# Power4.net
KiCad netlist of a schematic drawn in Altium Designer
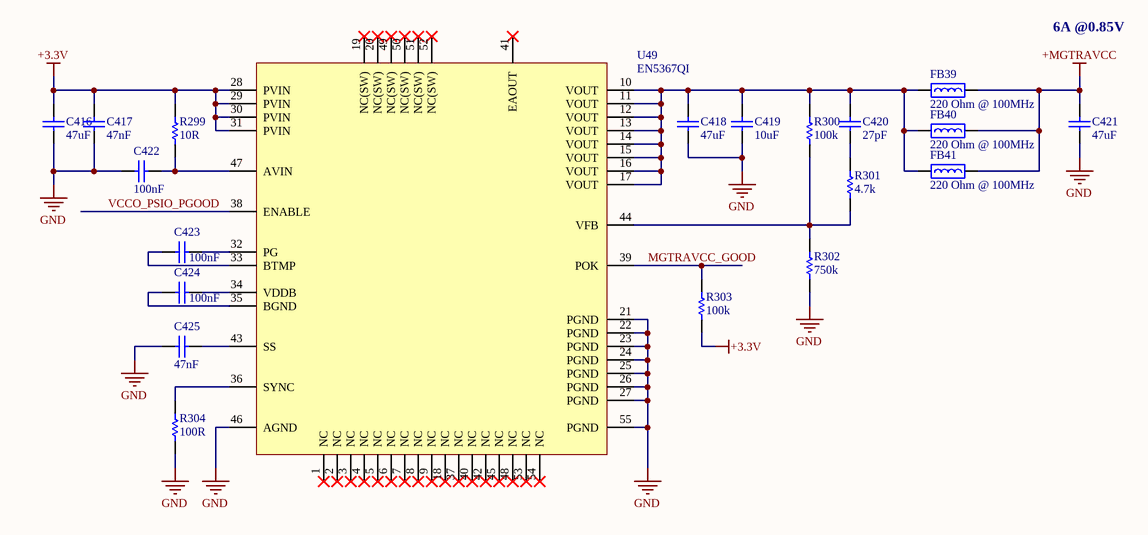
[diagram p0: Power4.SchDoc]

(export (version "E")
  (design (tool "Eeschema 10.0.6"))
  (components
    (comp (ref "C416")
      (value "47uF")
      (footprint "CAPC3216L_1206")
      (description "CAP CER 47UF 25V X5R 1206")
      (fields (field (name "VOLTAGE") "25V") (field (name "TOLERANCE") "20%"))
      (libsource (lib "Ultrascale_SchLib") (part "CAPCER1206X5R47U25V_20T"))
    )
    (comp (ref "C417")
      (value "47nF")
      (footprint "CAPC2012L_0805")
      (description "CAP CER 0.047UF 50V X7R 0805")
      (fields (field (name "VOLTAGE") "50V") (field (name "TOLERANCE") "10%"))
      (libsource (lib "Ultrascale_SchLib") (part "CAPCER0805X5R47N50V_10T"))
    )
    (comp (ref "C418")
      (value "47uF")
      (footprint "CAPC3216L_1206")
      (description "CAP CER 47UF 25V X5R 1206")
      (fields (field (name "VOLTAGE") "25V") (field (name "TOLERANCE") "20%"))
      (libsource (lib "Ultrascale_SchLib") (part "CAPCER1206X5R47U25V_20T"))
    )
    (comp (ref "C419")
      (value "10uF")
      (footprint "CAPC1005L_0402")
      (description "CAP CER 10UF 10V X5R 0402")
      (fields (field (name "VOLTAGE") "10V") (field (name "TOLERANCE") "20%"))
      (libsource (lib "Ultrascale_SchLib") (part "CAPCER0402X5R10U10V_20T"))
    )
    (comp (ref "C420")
      (value "27pF")
      (footprint "CAPC1005L_0402")
      (description "CAP CER 27PF 50V C0G/NP0 0402")
      (fields (field (name "VOLTAGE") "50V") (field (name "TOLERANCE") "5%"))
      (libsource (lib "Ultrascale_SchLib") (part "CAPCER0402C0G27P50V_5T"))
    )
    (comp (ref "C421")
      (value "47uF")
      (footprint "CAPC3216L_1206")
      (description "CAP CER 47UF 25V X5R 1206")
      (fields (field (name "VOLTAGE") "25V") (field (name "TOLERANCE") "20%"))
      (libsource (lib "Ultrascale_SchLib") (part "CAPCER1206X5R47U25V_20T"))
    )
    (comp (ref "C422")
      (value "100nF")
      (footprint "CAPC1005L_0402")
      (description "CAP CER 0.1UF 25V X7R 0402")
      (fields (field (name "VOLTAGE") "25V") (field (name "TOLERANCE") "10%"))
      (libsource (lib "Ultrascale_SchLib") (part "CAPCER0402X7R100N25V_10T"))
    )
    (comp (ref "C423")
      (value "100nF")
      (footprint "CAPC1005L_0402")
      (description "CAP CER 0.1UF 25V X7R 0402")
      (fields (field (name "VOLTAGE") "25V") (field (name "TOLERANCE") "10%"))
      (libsource (lib "Ultrascale_SchLib") (part "CAPCER0402X7R100N25V_10T"))
    )
    (comp (ref "C424")
      (value "100nF")
      (footprint "CAPC1005L_0402")
      (description "CAP CER 0.1UF 25V X7R 0402")
      (fields (field (name "VOLTAGE") "25V") (field (name "TOLERANCE") "10%"))
      (libsource (lib "Ultrascale_SchLib") (part "CAPCER0402X7R100N25V_10T"))
    )
    (comp (ref "C425")
      (value "47nF")
      (footprint "CAPC2012L_0805")
      (description "CAP CER 0.047UF 50V X7R 0805")
      (fields (field (name "VOLTAGE") "50V") (field (name "TOLERANCE") "10%"))
      (libsource (lib "Ultrascale_SchLib") (part "CAPCER0805X5R47N50V_10T"))
    )
    (comp (ref "FB39")
      (value "BEAD0603_220_2A5_40M")
      (footprint "INDC1608N_0603")
      (description "FERRITE BEAD 220 OHM 0603 1LN")
      (fields (field (name "IMPEDANCE @ FREQUENCY") "220 Ohm @ 100MHz"))
      (libsource (lib "Ultrascale_SchLib") (part "BEAD0603_220_2A5_40M"))
    )
    (comp (ref "FB40")
      (value "BEAD0603_220_2A5_40M")
      (footprint "INDC1608N_0603")
      (description "FERRITE BEAD 220 OHM 0603 1LN")
      (fields (field (name "IMPEDANCE @ FREQUENCY") "220 Ohm @ 100MHz"))
      (libsource (lib "Ultrascale_SchLib") (part "BEAD0603_220_2A5_40M"))
    )
    (comp (ref "FB41")
      (value "BEAD0603_220_2A5_40M")
      (footprint "INDC1608N_0603")
      (description "FERRITE BEAD 220 OHM 0603 1LN")
      (fields (field (name "IMPEDANCE @ FREQUENCY") "220 Ohm @ 100MHz"))
      (libsource (lib "Ultrascale_SchLib") (part "BEAD0603_220_2A5_40M"))
    )
    (comp (ref "R299")
      (value "10R")
      (footprint "RESC1005L_0402")
      (description "RES SMD 10 OHM 1% 1/10W 0402")
      (fields (field (name "POWER") "1/10W") (field (name "TOLERANCE") "1%"))
      (libsource (lib "Ultrascale_SchLib") (part "RES0402_10R_0W1_1T"))
    )
    (comp (ref "R300")
      (value "100k")
      (footprint "RESC1005L_0402")
      (description "RES SMD 100K OHM 1% 1/5W 0402")
      (fields (field (name "POWER") "1/5W") (field (name "TOLERANCE") "1%"))
      (libsource (lib "Ultrascale_SchLib") (part "RES0402_100K_0W2_1T"))
    )
    (comp (ref "R301")
      (value "4.7k")
      (footprint "RESC1005L_0402")
      (description "RES SMD 4.7K OHM 1% 1/10W 0402")
      (fields (field (name "POWER") "1/10W") (field (name "TOLERANCE") "1%"))
      (libsource (lib "Ultrascale_SchLib") (part "RES0402_4K7_0W1_1T"))
    )
    (comp (ref "R302")
      (value "750k")
      (footprint "RESC1005L_0402")
      (description "RES SMD 750K OHM 1% 1/10W 0402")
      (fields (field (name "POWER") "1/10W") (field (name "TOLERANCE") "1%"))
      (libsource (lib "Ultrascale_SchLib") (part "RES0402_750K_0W1_1T"))
    )
    (comp (ref "R303")
      (value "100k")
      (footprint "RESC1005L_0402")
      (description "RES SMD 100K OHM 1% 1/5W 0402")
      (fields (field (name "POWER") "1/5W") (field (name "TOLERANCE") "1%"))
      (libsource (lib "Ultrascale_SchLib") (part "RES0402_100K_0W2_1T"))
    )
    (comp (ref "R304")
      (value "100R")
      (footprint "RESC1005L_0402")
      (description "RES SMD 100 OHM 1% 1/10W 0402")
      (fields (field (name "POWER") "1/10W") (field (name "TOLERANCE") "1%"))
      (libsource (lib "Ultrascale_SchLib") (part "RES0402_100R_0W1_1T"))
    )
    (comp (ref "U49")
      (value "EN5367QI")
      (footprint "QFN54-EN5367QI")
      (description "DC/DC CONVERTER 0.6-4.9V 29W")
      (libsource (lib "Ultrascale_SchLib") (part "EN5367QI"))
    )
  )
  (nets
    (net (code "1") (name "+3.3V") (class "Default")
      (node (ref "C416") (pin "2") (pinfunction "2_2") (pintype "passive"))
      (node (ref "C417") (pin "2") (pinfunction "2_2") (pintype "passive"))
      (node (ref "R299") (pin "2") (pinfunction "2_2") (pintype "passive"))
      (node (ref "R303") (pin "2") (pinfunction "2_2") (pintype "passive"))
      (node (ref "U49") (pin "28") (pinfunction "PVIN_28") (pintype "power_in"))
      (node (ref "U49") (pin "29") (pinfunction "PVIN_29") (pintype "power_in"))
      (node (ref "U49") (pin "30") (pinfunction "PVIN_30") (pintype "power_in"))
      (node (ref "U49") (pin "31") (pinfunction "PVIN_31") (pintype "power_in"))
    )
    (net (code "2") (name "+MGTRAVCC") (class "Default")
      (node (ref "C421") (pin "2") (pinfunction "2_2") (pintype "passive"))
      (node (ref "FB39") (pin "2") (pinfunction "2_2") (pintype "passive"))
      (node (ref "FB40") (pin "2") (pinfunction "2_2") (pintype "passive"))
      (node (ref "FB41") (pin "2") (pinfunction "2_2") (pintype "passive"))
    )
    (net (code "3") (name "/MGTRAVCC_GOOD") (class "Default")
      (node (ref "R303") (pin "1") (pinfunction "1_1") (pintype "passive"))
      (node (ref "U49") (pin "39") (pinfunction "POK_39") (pintype "power_in"))
    )
    (net (code "4") (name "/VCCO_PSIO_PGOOD") (class "Default")
      (node (ref "U49") (pin "38") (pinfunction "ENABLE_38") (pintype "power_in"))
    )
    (net (code "5") (name "GND") (class "Default")
      (node (ref "C416") (pin "1") (pinfunction "1_1") (pintype "passive"))
      (node (ref "C417") (pin "1") (pinfunction "1_1") (pintype "passive"))
      (node (ref "C418") (pin "1") (pinfunction "1_1") (pintype "passive"))
      (node (ref "C419") (pin "1") (pinfunction "1_1") (pintype "passive"))
      (node (ref "C421") (pin "1") (pinfunction "1_1") (pintype "passive"))
      (node (ref "C422") (pin "2") (pinfunction "2_2") (pintype "passive"))
      (node (ref "C425") (pin "2") (pinfunction "2_2") (pintype "passive"))
      (node (ref "R302") (pin "1") (pinfunction "1_1") (pintype "passive"))
      (node (ref "R304") (pin "2") (pinfunction "2_2") (pintype "passive"))
      (node (ref "U49") (pin "21") (pinfunction "PGND_21") (pintype "power_in"))
      (node (ref "U49") (pin "22") (pinfunction "PGND_22") (pintype "power_in"))
      (node (ref "U49") (pin "23") (pinfunction "PGND_23") (pintype "power_in"))
      (node (ref "U49") (pin "24") (pinfunction "PGND_24") (pintype "power_in"))
      (node (ref "U49") (pin "25") (pinfunction "PGND_25") (pintype "power_in"))
      (node (ref "U49") (pin "26") (pinfunction "PGND_26") (pintype "power_in"))
      (node (ref "U49") (pin "27") (pinfunction "PGND_27") (pintype "power_in"))
      (node (ref "U49") (pin "46") (pinfunction "AGND_46") (pintype "power_in"))
      (node (ref "U49") (pin "55") (pinfunction "PGND_55") (pintype "power_in"))
    )
    (net (code "6") (name "Net-(C418-Pad2)") (class "Default")
      (node (ref "C418") (pin "2") (pinfunction "2_2") (pintype "passive"))
      (node (ref "C419") (pin "2") (pinfunction "2_2") (pintype "passive"))
      (node (ref "C420") (pin "2") (pinfunction "2_2") (pintype "passive"))
      (node (ref "FB39") (pin "1") (pinfunction "1_1") (pintype "passive"))
      (node (ref "FB40") (pin "1") (pinfunction "1_1") (pintype "passive"))
      (node (ref "FB41") (pin "1") (pinfunction "1_1") (pintype "passive"))
      (node (ref "R300") (pin "2") (pinfunction "2_2") (pintype "passive"))
      (node (ref "U49") (pin "10") (pinfunction "VOUT_10") (pintype "power_in"))
      (node (ref "U49") (pin "11") (pinfunction "VOUT_11") (pintype "power_in"))
      (node (ref "U49") (pin "12") (pinfunction "VOUT_12") (pintype "power_in"))
      (node (ref "U49") (pin "13") (pinfunction "VOUT_13") (pintype "power_in"))
      (node (ref "U49") (pin "14") (pinfunction "VOUT_14") (pintype "power_in"))
      (node (ref "U49") (pin "15") (pinfunction "VOUT_15") (pintype "power_in"))
      (node (ref "U49") (pin "16") (pinfunction "VOUT_16") (pintype "power_in"))
      (node (ref "U49") (pin "17") (pinfunction "VOUT_17") (pintype "power_in"))
    )
    (net (code "7") (name "Net-(C420-Pad1)") (class "Default")
      (node (ref "C420") (pin "1") (pinfunction "1_1") (pintype "passive"))
      (node (ref "R301") (pin "2") (pinfunction "2_2") (pintype "passive"))
    )
    (net (code "8") (name "Net-(U49-AVIN)") (class "Default")
      (node (ref "C422") (pin "1") (pinfunction "1_1") (pintype "passive"))
      (node (ref "R299") (pin "1") (pinfunction "1_1") (pintype "passive"))
      (node (ref "U49") (pin "47") (pinfunction "AVIN_47") (pintype "power_in"))
    )
    (net (code "9") (name "Net-(U49-BGND)") (class "Default")
      (node (ref "C424") (pin "2") (pinfunction "2_2") (pintype "passive"))
      (node (ref "U49") (pin "35") (pinfunction "BGND_35") (pintype "power_in"))
    )
    (net (code "10") (name "Net-(U49-BTMP)") (class "Default")
      (node (ref "C423") (pin "2") (pinfunction "2_2") (pintype "passive"))
      (node (ref "U49") (pin "33") (pinfunction "BTMP_33") (pintype "power_in"))
    )
    (net (code "11") (name "Net-(U49-PG)") (class "Default")
      (node (ref "C423") (pin "1") (pinfunction "1_1") (pintype "passive"))
      (node (ref "U49") (pin "32") (pinfunction "PG_32") (pintype "power_in"))
    )
    (net (code "12") (name "Net-(U49-SS)") (class "Default")
      (node (ref "C425") (pin "1") (pinfunction "1_1") (pintype "passive"))
      (node (ref "U49") (pin "43") (pinfunction "SS_43") (pintype "power_in"))
    )
    (net (code "13") (name "Net-(U49-SYNC)") (class "Default")
      (node (ref "R304") (pin "1") (pinfunction "1_1") (pintype "passive"))
      (node (ref "U49") (pin "36") (pinfunction "SYNC_36") (pintype "power_in"))
    )
    (net (code "14") (name "Net-(U49-VDDB)") (class "Default")
      (node (ref "C424") (pin "1") (pinfunction "1_1") (pintype "passive"))
      (node (ref "U49") (pin "34") (pinfunction "VDDB_34") (pintype "power_in"))
    )
    (net (code "15") (name "Net-(U49-VFB)") (class "Default")
      (node (ref "R300") (pin "1") (pinfunction "1_1") (pintype "passive"))
      (node (ref "R301") (pin "1") (pinfunction "1_1") (pintype "passive"))
      (node (ref "R302") (pin "2") (pinfunction "2_2") (pintype "passive"))
      (node (ref "U49") (pin "44") (pinfunction "VFB_44") (pintype "power_in"))
    )
    (net (code "16") (name "unconnected-(U49-EAOUT-Pad41)") (class "Default")
      (node (ref "U49") (pin "41") (pinfunction "EAOUT_41") (pintype "power_in+no_connect"))
    )
    (net (code "17") (name "unconnected-(U49-NC(SW)-Pad19)") (class "Default")
      (node (ref "U49") (pin "19") (pinfunction "NC(SW)_19") (pintype "power_in+no_connect"))
    )
    (net (code "18") (name "unconnected-(U49-NC(SW)-Pad20)") (class "Default")
      (node (ref "U49") (pin "20") (pinfunction "NC(SW)_20") (pintype "power_in+no_connect"))
    )
    (net (code "19") (name "unconnected-(U49-NC(SW)-Pad49)") (class "Default")
      (node (ref "U49") (pin "49") (pinfunction "NC(SW)_49") (pintype "power_in+no_connect"))
    )
    (net (code "20") (name "unconnected-(U49-NC(SW)-Pad50)") (class "Default")
      (node (ref "U49") (pin "50") (pinfunction "NC(SW)_50") (pintype "power_in+no_connect"))
    )
    (net (code "21") (name "unconnected-(U49-NC(SW)-Pad51)") (class "Default")
      (node (ref "U49") (pin "51") (pinfunction "NC(SW)_51") (pintype "power_in+no_connect"))
    )
    (net (code "22") (name "unconnected-(U49-NC(SW)-Pad52)") (class "Default")
      (node (ref "U49") (pin "52") (pinfunction "NC(SW)_52") (pintype "power_in+no_connect"))
    )
    (net (code "23") (name "unconnected-(U49-NC-Pad1)") (class "Default")
      (node (ref "U49") (pin "1") (pinfunction "NC_1") (pintype "power_in+no_connect"))
    )
    (net (code "24") (name "unconnected-(U49-NC-Pad2)") (class "Default")
      (node (ref "U49") (pin "2") (pinfunction "NC_2") (pintype "power_in+no_connect"))
    )
    (net (code "25") (name "unconnected-(U49-NC-Pad3)") (class "Default")
      (node (ref "U49") (pin "3") (pinfunction "NC_3") (pintype "power_in+no_connect"))
    )
    (net (code "26") (name "unconnected-(U49-NC-Pad4)") (class "Default")
      (node (ref "U49") (pin "4") (pinfunction "NC_4") (pintype "power_in+no_connect"))
    )
    (net (code "27") (name "unconnected-(U49-NC-Pad5)") (class "Default")
      (node (ref "U49") (pin "5") (pinfunction "NC_5") (pintype "power_in+no_connect"))
    )
    (net (code "28") (name "unconnected-(U49-NC-Pad6)") (class "Default")
      (node (ref "U49") (pin "6") (pinfunction "NC_6") (pintype "power_in+no_connect"))
    )
    (net (code "29") (name "unconnected-(U49-NC-Pad7)") (class "Default")
      (node (ref "U49") (pin "7") (pinfunction "NC_7") (pintype "power_in+no_connect"))
    )
    (net (code "30") (name "unconnected-(U49-NC-Pad8)") (class "Default")
      (node (ref "U49") (pin "8") (pinfunction "NC_8") (pintype "power_in+no_connect"))
    )
    (net (code "31") (name "unconnected-(U49-NC-Pad9)") (class "Default")
      (node (ref "U49") (pin "9") (pinfunction "NC_9") (pintype "power_in+no_connect"))
    )
    (net (code "32") (name "unconnected-(U49-NC-Pad18)") (class "Default")
      (node (ref "U49") (pin "18") (pinfunction "NC_18") (pintype "power_in+no_connect"))
    )
    (net (code "33") (name "unconnected-(U49-NC-Pad37)") (class "Default")
      (node (ref "U49") (pin "37") (pinfunction "NC_37") (pintype "power_in+no_connect"))
    )
    (net (code "34") (name "unconnected-(U49-NC-Pad40)") (class "Default")
      (node (ref "U49") (pin "40") (pinfunction "NC_40") (pintype "power_in+no_connect"))
    )
    (net (code "35") (name "unconnected-(U49-NC-Pad42)") (class "Default")
      (node (ref "U49") (pin "42") (pinfunction "NC_42") (pintype "power_in+no_connect"))
    )
    (net (code "36") (name "unconnected-(U49-NC-Pad45)") (class "Default")
      (node (ref "U49") (pin "45") (pinfunction "NC_45") (pintype "power_in+no_connect"))
    )
    (net (code "37") (name "unconnected-(U49-NC-Pad48)") (class "Default")
      (node (ref "U49") (pin "48") (pinfunction "NC_48") (pintype "power_in+no_connect"))
    )
    (net (code "38") (name "unconnected-(U49-NC-Pad53)") (class "Default")
      (node (ref "U49") (pin "53") (pinfunction "NC_53") (pintype "power_in+no_connect"))
    )
    (net (code "39") (name "unconnected-(U49-NC-Pad54)") (class "Default")
      (node (ref "U49") (pin "54") (pinfunction "NC_54") (pintype "power_in+no_connect"))
    )
  )
)
